# SunS_fixture_EGSE_Connectors.net
KiCad netlist of a schematic drawn in Altium Designer
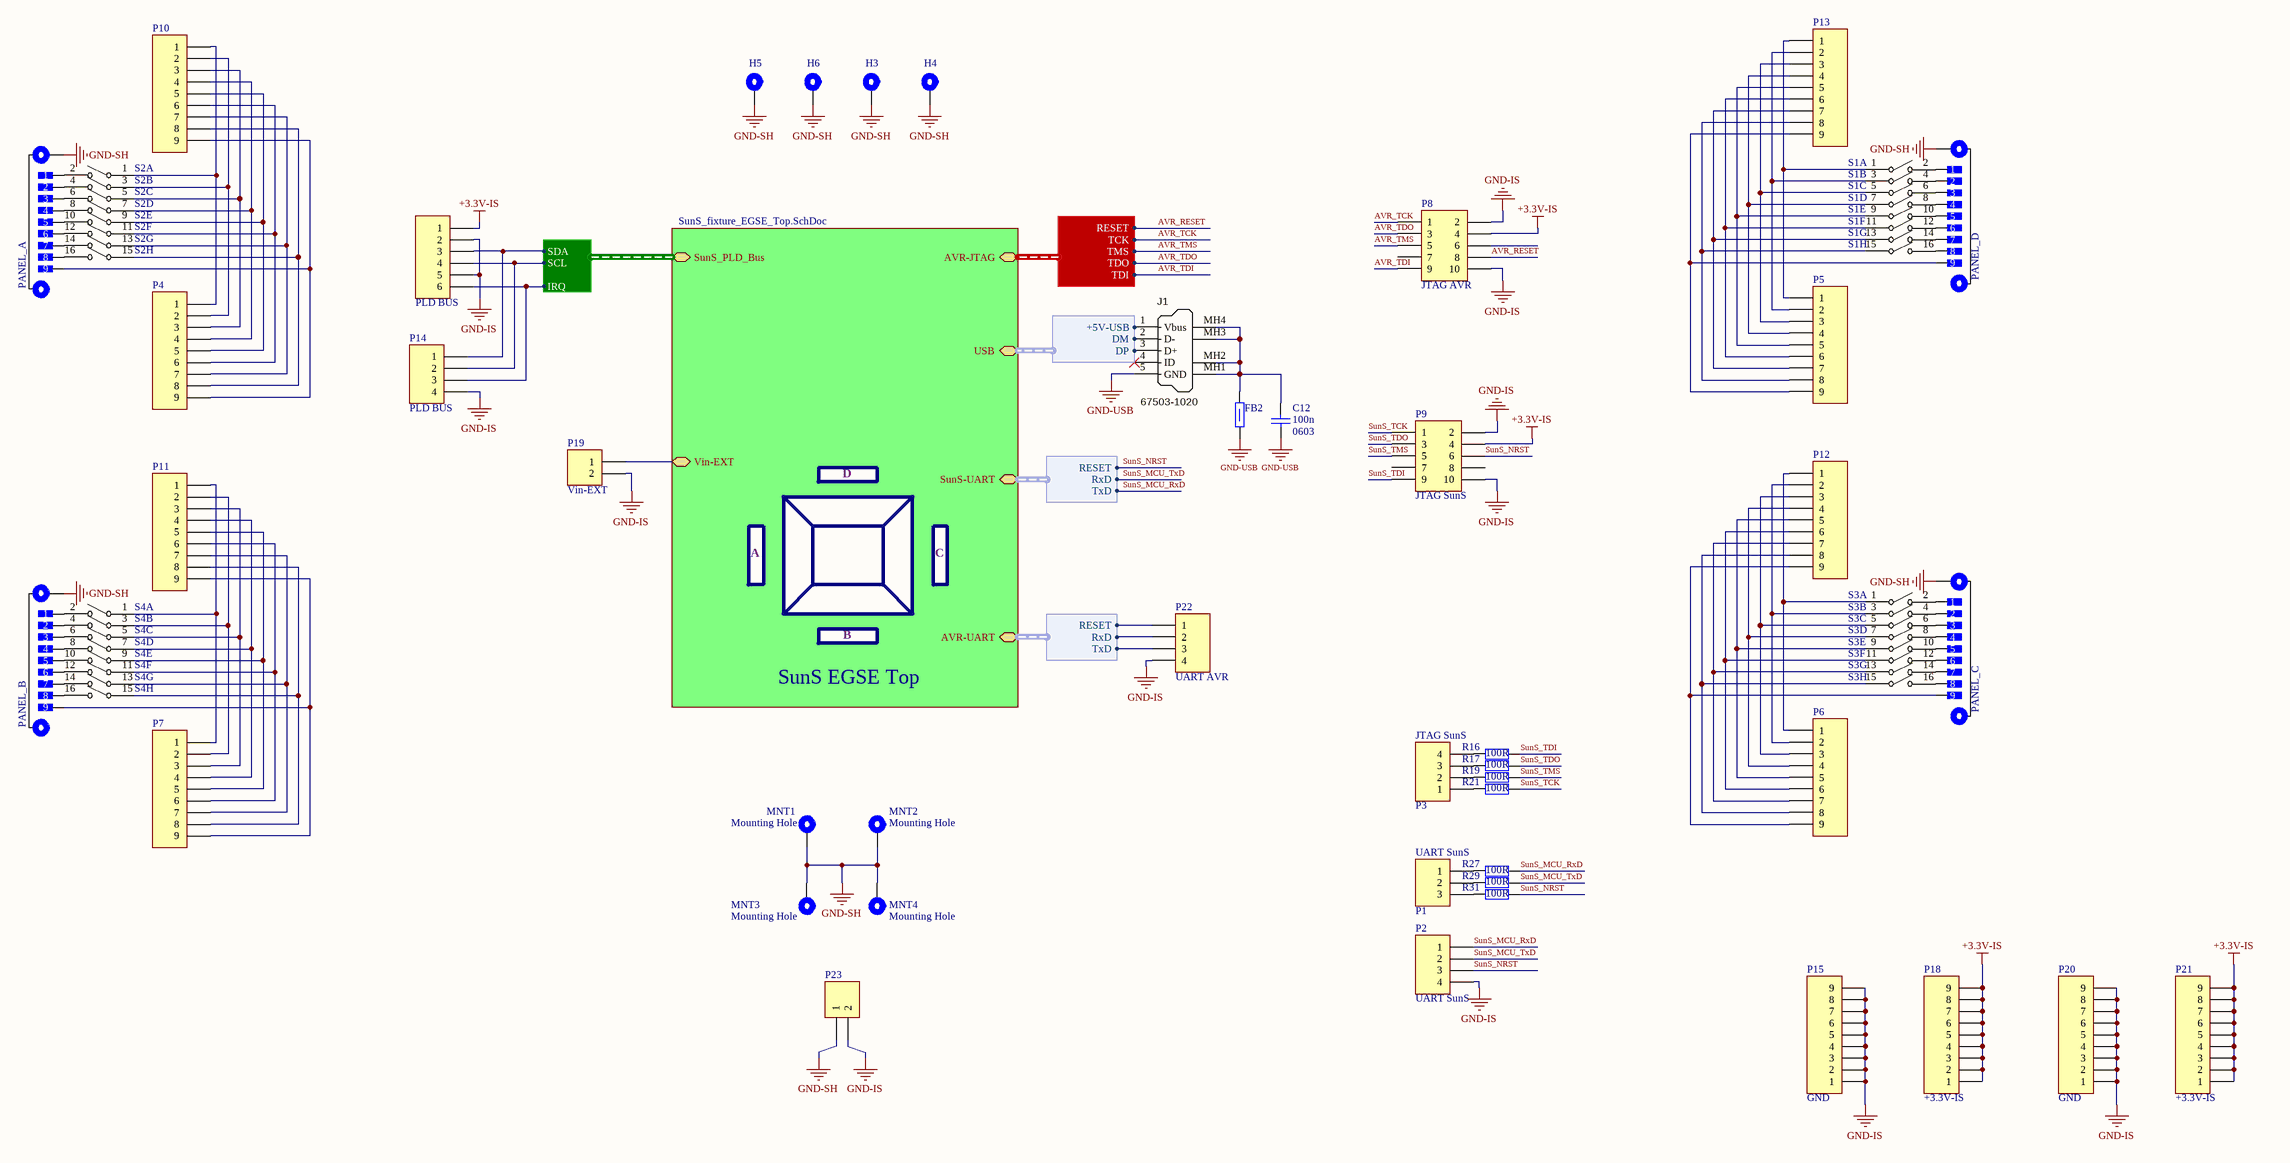
[diagram p0: SunS_fixture_EGSE_Connectors.SchDoc]

(export (version "E")
  (design (tool "Eeschema 10.0.6"))
  (components
    (comp (ref "C12")
      (value "100n")
      (footprint "SMD_Capacitor_0603")
      (description "Cap")
      (fields (field (name "PACKAGE") "0603"))
      (libsource (lib "capacitors") (part "Cap"))
    )
    (comp (ref "FB2")
      (value "120R/100MHz")
      (footprint "SMD_FerriteBead_1206")
      (description "Ferrite bead, 1206, 0.02HM, 3.5A.")
      (fields (field (name "MANUFACTURER") "Murata") (field (name "MANUFACTURERPARTNUMBER") "BLM31PG121SH1L"))
      (libsource (lib "inductors") (part "BLM31PG121SH1L"))
    )
    (comp (ref "H3")
      (value "Mounting Hole")
      (footprint "SunS_PcbMntHole_M2")
      (description "PCB Mounting Hole")
      (libsource (lib "connectors_printed-circuit-board") (part "MntHole"))
    )
    (comp (ref "H4")
      (value "Mounting Hole")
      (footprint "SunS_PcbMntHole_M2")
      (description "PCB Mounting Hole")
      (libsource (lib "connectors_printed-circuit-board") (part "MntHole"))
    )
    (comp (ref "H5")
      (value "Mounting Hole")
      (footprint "SunS_PcbMntHole_M2")
      (description "PCB Mounting Hole")
      (libsource (lib "connectors_printed-circuit-board") (part "MntHole"))
    )
    (comp (ref "H6")
      (value "Mounting Hole")
      (footprint "SunS_PcbMntHole_M2")
      (description "PCB Mounting Hole")
      (libsource (lib "connectors_printed-circuit-board") (part "MntHole"))
    )
    (comp (ref "J1")
      (value "USB_Mini-B")
      (footprint "USB_Mini-B_Molex_SMT")
      (description "Connector SMD USB Type Mini-B")
      (fields (field (name "MANUFACTURER PART NUMBER 1") "67503-1020"))
      (libsource (lib "PBL - Connectors") (part "USB_Mini-B"))
    )
    (comp (ref "MNT1")
      (value "Mounting Hole")
      (footprint "PC-104_PcbMntHole_M3")
      (description "PCB Mounting Hole")
      (libsource (lib "connectors_printed-circuit-board") (part "MntHole"))
    )
    (comp (ref "MNT2")
      (value "Mounting Hole")
      (footprint "PC-104_PcbMntHole_M3")
      (description "PCB Mounting Hole")
      (libsource (lib "connectors_printed-circuit-board") (part "MntHole"))
    )
    (comp (ref "MNT3")
      (value "Mounting Hole")
      (footprint "PC-104_PcbMntHole_M3")
      (description "PCB Mounting Hole")
      (libsource (lib "connectors_printed-circuit-board") (part "MntHole"))
    )
    (comp (ref "MNT4")
      (value "Mounting Hole")
      (footprint "PC-104_PcbMntHole_M3")
      (description "PCB Mounting Hole")
      (libsource (lib "connectors_printed-circuit-board") (part "MntHole"))
    )
    (comp (ref "P1")
      (value "UART SunS")
      (footprint "Mill-Max 854-22-003-10-001101")
      (description "SPRING-LOADED CONNECTORS, 854-22-003-10-001101, 1.27 mm pitch, 1x3pin, THT")
      (libsource (lib "connectors_printed-circuit-board") (part "Mill-Max 854-22-003-10-001101"))
    )
    (comp (ref "P2")
      (value "UART SunS")
      (footprint "HEADER 1x4 MALE")
      (description "Header, 4-Pin")
      (fields (field (name "PUBLISHER") "Altium Limited"))
      (libsource (lib "") (part "Header 4_1"))
    )
    (comp (ref "P3")
      (value "JTAG SunS")
      (footprint "Mill-Max 854-22-004-10-001101")
      (description "SPRING-LOADED CONNECTORS, 854-22-004-10-001101, 1.27 mm pitch, 1x4pin, THT.")
      (libsource (lib "connectors_printed-circuit-board") (part "Mill-Max 854-22-004-10-001101"))
    )
    (comp (ref "P4")
      (value "Mill-Max 854-22-009-10-001101")
      (footprint "Mill-Max 854-22-009-10-001101")
      (description "SPRING-LOADED CONNECTORS, 854-22-009-10-001101, 1.27 mm pitch, 1x9pin, THT.")
      (libsource (lib "") (part "Mill-Max 854-22-009-10-001101_1"))
    )
    (comp (ref "P5")
      (value "Mill-Max 854-22-009-10-001101")
      (footprint "Mill-Max 854-22-009-10-001101")
      (description "SPRING-LOADED CONNECTORS, 854-22-009-10-001101, 1.27 mm pitch, 1x9pin, THT.")
      (libsource (lib "connectors_printed-circuit-board") (part "Mill-Max 854-22-009-10-001101"))
    )
    (comp (ref "P6")
      (value "Mill-Max 854-22-009-10-001101")
      (footprint "Mill-Max 854-22-009-10-001101")
      (description "SPRING-LOADED CONNECTORS, 854-22-009-10-001101, 1.27 mm pitch, 1x9pin, THT.")
      (libsource (lib "connectors_printed-circuit-board") (part "Mill-Max 854-22-009-10-001101"))
    )
    (comp (ref "P7")
      (value "Mill-Max 854-22-009-10-001101")
      (footprint "Mill-Max 854-22-009-10-001101")
      (description "SPRING-LOADED CONNECTORS, 854-22-009-10-001101, 1.27 mm pitch, 1x9pin, THT.")
      (libsource (lib "") (part "Mill-Max 854-22-009-10-001101_1"))
    )
    (comp (ref "P8")
      (value "JTAG AVR")
      (footprint "IDC-10-Male-Socket")
      (description "Header, 5-Pin, Dual row")
      (libsource (lib "connectors_printed-circuit-board") (part "Header 5X2"))
    )
    (comp (ref "P9")
      (value "JTAG SunS")
      (footprint "IDC-10-Male-Socket")
      (description "Header, 5-Pin, Dual row")
      (libsource (lib "connectors_printed-circuit-board") (part "Header 5X2"))
    )
    (comp (ref "P10")
      (value "Header 9")
      (footprint "HEADER 1x9 MALE")
      (description "Header, 9-Pin")
      (fields (field (name "PUBLISHER") "Altium Limited"))
      (libsource (lib "") (part "Header 9_2"))
    )
    (comp (ref "P11")
      (value "Header 9")
      (footprint "HEADER 1x9 MALE")
      (description "Header, 9-Pin")
      (fields (field (name "PUBLISHER") "Altium Limited"))
      (libsource (lib "") (part "Header 9_2"))
    )
    (comp (ref "P12")
      (value "Header 9")
      (footprint "HEADER 1x9 MALE")
      (description "Header, 9-Pin")
      (fields (field (name "PUBLISHER") "Altium Limited"))
      (libsource (lib "") (part "Header 9_1"))
    )
    (comp (ref "P13")
      (value "Header 9")
      (footprint "HEADER 1x9 MALE")
      (description "Header, 9-Pin")
      (fields (field (name "PUBLISHER") "Altium Limited"))
      (libsource (lib "") (part "Header 9_1"))
    )
    (comp (ref "P14")
      (value "PLD BUS")
      (footprint "HEADER 1x4 MALE")
      (description "Header, 4-Pin")
      (fields (field (name "PUBLISHER") "Altium Limited"))
      (libsource (lib "connectors_printed-circuit-board") (part "Header 4x1"))
    )
    (comp (ref "P15")
      (value "GND")
      (footprint "HEADER 1x9 MALE")
      (description "Header, 9-Pin")
      (fields (field (name "PUBLISHER") "Altium Limited"))
      (libsource (lib "connectors_printed-circuit-board") (part "Header 9"))
    )
    (comp (ref "P18")
      (value "+3.3V-IS")
      (footprint "HEADER 1x9 MALE")
      (description "Header, 9-Pin")
      (fields (field (name "PUBLISHER") "Altium Limited"))
      (libsource (lib "connectors_printed-circuit-board") (part "Header 9"))
    )
    (comp (ref "P19")
      (value "Vin-EXT")
      (footprint "HEADER 1X2H Male")
      (description "Header, 2-Pin")
      (fields (field (name "PUBLISHER") "Altium Limited"))
      (libsource (lib "connectors_printed-circuit-board") (part "Header 2"))
    )
    (comp (ref "P20")
      (value "GND")
      (footprint "HEADER 1x9 MALE")
      (description "Header, 9-Pin")
      (fields (field (name "PUBLISHER") "Altium Limited"))
      (libsource (lib "connectors_printed-circuit-board") (part "Header 9"))
    )
    (comp (ref "P21")
      (value "+3.3V-IS")
      (footprint "HEADER 1x9 MALE")
      (description "Header, 9-Pin")
      (fields (field (name "PUBLISHER") "Altium Limited"))
      (libsource (lib "connectors_printed-circuit-board") (part "Header 9"))
    )
    (comp (ref "P22")
      (value "UART AVR")
      (footprint "HEADER 1x4 MALE")
      (description "Header, 4-Pin")
      (fields (field (name "PUBLISHER") "Altium Limited"))
      (libsource (lib "connectors_printed-circuit-board") (part "Header 4"))
    )
    (comp (ref "P23")
      (value "Header 2")
      (footprint "HEADER 1X2 Male")
      (description "Header, 2-Pin")
      (fields (field (name "PUBLISHER") "Altium Limited"))
      (libsource (lib "") (part "Header 2_1"))
    )
    (comp (ref "PANEL_A")
      (value "fixture_ALS_9_pad_1mm_pitch")
      (footprint "fixture_ALS_9_pad_1mm_pitch")
      (description "ALS Panel Fixture Connection")
      (libsource (lib "connectors_printed-circuit-board") (part "fixture_ALS_9_pad_1mm_pitch"))
    )
    (comp (ref "PANEL_B")
      (value "fixture_ALS_9_pad_1mm_pitch")
      (footprint "fixture_ALS_9_pad_1mm_pitch")
      (description "ALS Panel Fixture Connection")
      (libsource (lib "connectors_printed-circuit-board") (part "fixture_ALS_9_pad_1mm_pitch"))
    )
    (comp (ref "PANEL_C")
      (value "fixture_ALS_9_pad_1mm_pitch")
      (footprint "fixture_ALS_9_pad_1mm_pitch")
      (description "ALS Panel Fixture Connection")
      (libsource (lib "") (part "fixture_ALS_9_pad_1mm_pitch_1"))
    )
    (comp (ref "PANEL_D")
      (value "fixture_ALS_9_pad_1mm_pitch")
      (footprint "fixture_ALS_9_pad_1mm_pitch")
      (description "ALS Panel Fixture Connection")
      (libsource (lib "") (part "fixture_ALS_9_pad_1mm_pitch_1"))
    )
    (comp (ref "PLD BUS")
      (value "Mill-Max 854-22-006-10-001101")
      (footprint "Mill-Max 854-22-006-10-001101")
      (description "SPRING-LOADED CONNECTORS, 854-22-006-10-001101, 1.27 mm pitch, 1x6pin, THT.")
      (libsource (lib "connectors_printed-circuit-board") (part "Mill-Max 854-22-006-10-001101"))
    )
    (comp (ref "R16")
      (value "100R")
      (footprint "SMD_Resistor_0603")
      (libsource (lib "resistors") (part "Res"))
    )
    (comp (ref "R17")
      (value "100R")
      (footprint "SMD_Resistor_0603")
      (libsource (lib "resistors") (part "Res"))
    )
    (comp (ref "R19")
      (value "100R")
      (footprint "SMD_Resistor_0603")
      (libsource (lib "resistors") (part "Res"))
    )
    (comp (ref "R21")
      (value "100R")
      (footprint "SMD_Resistor_0603")
      (libsource (lib "resistors") (part "Res"))
    )
    (comp (ref "R27")
      (value "100R")
      (footprint "SMD_Resistor_0603")
      (libsource (lib "resistors") (part "Res"))
    )
    (comp (ref "R29")
      (value "100R")
      (footprint "SMD_Resistor_0603")
      (libsource (lib "resistors") (part "Res"))
    )
    (comp (ref "R31")
      (value "100R")
      (footprint "SMD_Resistor_0603")
      (libsource (lib "resistors") (part "Res"))
    )
    (comp (ref "S1") (value "MCEPM-08") (footprint "MCEPM-08") (libsource (lib "switches") (part "MCEPM-08")))
    (comp (ref "S2") (value "MCEPM-08") (footprint "MCEPM-08") (libsource (lib "") (part "MCEPM-08_7")))
    (comp (ref "S3") (value "MCEPM-08") (footprint "MCEPM-08") (libsource (lib "switches") (part "MCEPM-08")))
    (comp (ref "S4") (value "MCEPM-08") (footprint "MCEPM-08") (libsource (lib "") (part "MCEPM-08_5")))
  )
  (nets
    (net (code "5") (name "+3.3V-IS") (class "Default")
      (node (ref "P18") (pin "1") (pinfunction "1_1") (pintype "passive"))
      (node (ref "P18") (pin "2") (pinfunction "2_2") (pintype "passive"))
      (node (ref "P18") (pin "3") (pinfunction "3_3") (pintype "passive"))
      (node (ref "P18") (pin "4") (pinfunction "4_4") (pintype "passive"))
      (node (ref "P18") (pin "5") (pinfunction "5_5") (pintype "passive"))
      (node (ref "P18") (pin "6") (pinfunction "6_6") (pintype "passive"))
      (node (ref "P18") (pin "7") (pinfunction "7_7") (pintype "passive"))
      (node (ref "P18") (pin "8") (pinfunction "8_8") (pintype "passive"))
      (node (ref "P18") (pin "9") (pinfunction "9_9") (pintype "passive"))
      (node (ref "P21") (pin "1") (pinfunction "1_1") (pintype "passive"))
      (node (ref "P21") (pin "2") (pinfunction "2_2") (pintype "passive"))
      (node (ref "P21") (pin "3") (pinfunction "3_3") (pintype "passive"))
      (node (ref "P21") (pin "4") (pinfunction "4_4") (pintype "passive"))
      (node (ref "P21") (pin "5") (pinfunction "5_5") (pintype "passive"))
      (node (ref "P21") (pin "6") (pinfunction "6_6") (pintype "passive"))
      (node (ref "P21") (pin "7") (pinfunction "7_7") (pintype "passive"))
      (node (ref "P21") (pin "8") (pinfunction "8_8") (pintype "passive"))
      (node (ref "P21") (pin "9") (pinfunction "9_9") (pintype "passive"))
      (node (ref "P8") (pin "4") (pinfunction "4_4") (pintype "passive"))
      (node (ref "P9") (pin "4") (pinfunction "4_4") (pintype "passive"))
      (node (ref "PLD BUS") (pin "1") (pinfunction "1_1") (pintype "passive"))
    )
    (net (code "6") (name "/+5V-USB") (class "Default")
      (node (ref "J1") (pin "1") (pinfunction "Vbus_1") (pintype "passive"))
    )
    (net (code "7") (name "/AVR_RESET") (class "Default")
      (node (ref "P8") (pin "8") (pinfunction "8_8") (pintype "passive"))
    )
    (net (code "8") (name "/AVR_TCK") (class "Default")
      (node (ref "P8") (pin "1") (pinfunction "1_1") (pintype "passive"))
    )
    (net (code "9") (name "/AVR_TDI") (class "Default")
      (node (ref "P8") (pin "9") (pinfunction "9_9") (pintype "passive"))
    )
    (net (code "10") (name "/AVR_TDO") (class "Default")
      (node (ref "P8") (pin "3") (pinfunction "3_3") (pintype "passive"))
    )
    (net (code "11") (name "/AVR_TMS") (class "Default")
      (node (ref "P8") (pin "5") (pinfunction "5_5") (pintype "passive"))
    )
    (net (code "12") (name "/DM") (class "Default")
      (node (ref "J1") (pin "2") (pinfunction "D-_2") (pintype "passive"))
    )
    (net (code "13") (name "/DP") (class "Default")
      (node (ref "J1") (pin "3") (pinfunction "D+_3") (pintype "passive"))
    )
    (net (code "14") (name "/IRQ") (class "Default")
      (node (ref "P14") (pin "3") (pinfunction "3_3") (pintype "passive"))
      (node (ref "PLD BUS") (pin "6") (pinfunction "6_6") (pintype "passive"))
    )
    (net (code "15") (name "/SCL") (class "Default")
      (node (ref "P14") (pin "2") (pinfunction "2_2") (pintype "passive"))
      (node (ref "PLD BUS") (pin "4") (pinfunction "4_4") (pintype "passive"))
    )
    (net (code "16") (name "/SDA") (class "Default")
      (node (ref "P14") (pin "1") (pinfunction "1_1") (pintype "passive"))
      (node (ref "PLD BUS") (pin "3") (pinfunction "3_3") (pintype "passive"))
    )
    (net (code "17") (name "/SunS_MCU_RxD") (class "Default")
      (node (ref "P2") (pin "1") (pinfunction "1_1") (pintype "passive"))
      (node (ref "R27") (pin "1") (pinfunction "1_1") (pintype "passive"))
    )
    (net (code "18") (name "/SunS_MCU_TxD") (class "Default")
      (node (ref "P2") (pin "2") (pinfunction "2_2") (pintype "passive"))
      (node (ref "R29") (pin "1") (pinfunction "1_1") (pintype "passive"))
    )
    (net (code "19") (name "/SunS_NRST") (class "Default")
      (node (ref "P2") (pin "3") (pinfunction "3_3") (pintype "passive"))
      (node (ref "P9") (pin "6") (pinfunction "6_6") (pintype "passive"))
      (node (ref "R31") (pin "1") (pinfunction "1_1") (pintype "passive"))
    )
    (net (code "20") (name "/SunS_TCK") (class "Default")
      (node (ref "P9") (pin "1") (pinfunction "1_1") (pintype "passive"))
      (node (ref "R21") (pin "1") (pinfunction "1_1") (pintype "passive"))
    )
    (net (code "21") (name "/SunS_TDI") (class "Default")
      (node (ref "P9") (pin "9") (pinfunction "9_9") (pintype "passive"))
      (node (ref "R16") (pin "1") (pinfunction "1_1") (pintype "passive"))
    )
    (net (code "22") (name "/SunS_TDO") (class "Default")
      (node (ref "P9") (pin "3") (pinfunction "3_3") (pintype "passive"))
      (node (ref "R17") (pin "1") (pinfunction "1_1") (pintype "passive"))
    )
    (net (code "23") (name "/SunS_TMS") (class "Default")
      (node (ref "P9") (pin "5") (pinfunction "5_5") (pintype "passive"))
      (node (ref "R19") (pin "1") (pinfunction "1_1") (pintype "passive"))
    )
    (net (code "24") (name "/Vin-EXT") (class "Default")
      (node (ref "P19") (pin "1") (pinfunction "1_1") (pintype "passive"))
    )
    (net (code "29") (name "GND-IS") (class "Default")
      (node (ref "P14") (pin "4") (pinfunction "4_4") (pintype "passive"))
      (node (ref "P15") (pin "1") (pinfunction "1_1") (pintype "passive"))
      (node (ref "P15") (pin "2") (pinfunction "2_2") (pintype "passive"))
      (node (ref "P15") (pin "3") (pinfunction "3_3") (pintype "passive"))
      (node (ref "P15") (pin "4") (pinfunction "4_4") (pintype "passive"))
      (node (ref "P15") (pin "5") (pinfunction "5_5") (pintype "passive"))
      (node (ref "P15") (pin "6") (pinfunction "6_6") (pintype "passive"))
      (node (ref "P15") (pin "7") (pinfunction "7_7") (pintype "passive"))
      (node (ref "P15") (pin "8") (pinfunction "8_8") (pintype "passive"))
      (node (ref "P15") (pin "9") (pinfunction "9_9") (pintype "passive"))
      (node (ref "P19") (pin "2") (pinfunction "2_2") (pintype "passive"))
      (node (ref "P2") (pin "4") (pinfunction "4_4") (pintype "passive"))
      (node (ref "P20") (pin "1") (pinfunction "1_1") (pintype "passive"))
      (node (ref "P20") (pin "2") (pinfunction "2_2") (pintype "passive"))
      (node (ref "P20") (pin "3") (pinfunction "3_3") (pintype "passive"))
      (node (ref "P20") (pin "4") (pinfunction "4_4") (pintype "passive"))
      (node (ref "P20") (pin "5") (pinfunction "5_5") (pintype "passive"))
      (node (ref "P20") (pin "6") (pinfunction "6_6") (pintype "passive"))
      (node (ref "P20") (pin "7") (pinfunction "7_7") (pintype "passive"))
      (node (ref "P20") (pin "8") (pinfunction "8_8") (pintype "passive"))
      (node (ref "P20") (pin "9") (pinfunction "9_9") (pintype "passive"))
      (node (ref "P22") (pin "4") (pinfunction "4_4") (pintype "passive"))
      (node (ref "P23") (pin "2") (pinfunction "2_2") (pintype "passive"))
      (node (ref "P8") (pin "10") (pinfunction "10_10") (pintype "passive"))
      (node (ref "P8") (pin "2") (pinfunction "2_2") (pintype "passive"))
      (node (ref "P9") (pin "10") (pinfunction "10_10") (pintype "passive"))
      (node (ref "P9") (pin "2") (pinfunction "2_2") (pintype "passive"))
      (node (ref "PLD BUS") (pin "2") (pinfunction "2_2") (pintype "passive"))
      (node (ref "PLD BUS") (pin "5") (pinfunction "5_5") (pintype "passive"))
    )
    (net (code "30") (name "GND-SH") (class "Default")
      (node (ref "H3") (pin "1") (pinfunction "1_1") (pintype "passive"))
      (node (ref "H4") (pin "1") (pinfunction "1_1") (pintype "passive"))
      (node (ref "H5") (pin "1") (pinfunction "1_1") (pintype "passive"))
      (node (ref "H6") (pin "1") (pinfunction "1_1") (pintype "passive"))
      (node (ref "MNT1") (pin "1") (pinfunction "1_1") (pintype "passive"))
      (node (ref "MNT2") (pin "1") (pinfunction "1_1") (pintype "passive"))
      (node (ref "MNT3") (pin "1") (pinfunction "1_1") (pintype "passive"))
      (node (ref "MNT4") (pin "1") (pinfunction "1_1") (pintype "passive"))
      (node (ref "P23") (pin "1") (pinfunction "1_1") (pintype "passive"))
      (node (ref "PANEL_A") (pin "0") (pinfunction "0_0") (pintype "passive"))
      (node (ref "PANEL_B") (pin "0") (pinfunction "0_0") (pintype "passive"))
      (node (ref "PANEL_C") (pin "0") (pinfunction "0_0") (pintype "passive"))
      (node (ref "PANEL_D") (pin "0") (pinfunction "0_0") (pintype "passive"))
    )
    (net (code "31") (name "GND-USB") (class "Default")
      (node (ref "C12") (pin "2") (pinfunction "2_2") (pintype "passive"))
      (node (ref "FB2") (pin "2") (pinfunction "2_2") (pintype "passive"))
      (node (ref "J1") (pin "5") (pinfunction "GND_5") (pintype "passive"))
    )
    (net (code "32") (name "Net-(C12-Pad1)") (class "Default")
      (node (ref "C12") (pin "1") (pinfunction "1_1") (pintype "passive"))
      (node (ref "FB2") (pin "1") (pinfunction "1_1") (pintype "passive"))
      (node (ref "J1") (pin "MH1") (pinfunction "Shell_MH1") (pintype "passive"))
      (node (ref "J1") (pin "MH2") (pinfunction "Shell_MH2") (pintype "passive"))
      (node (ref "J1") (pin "MH3") (pinfunction "Shell_MH3") (pintype "passive"))
      (node (ref "J1") (pin "MH4") (pinfunction "Shell_MH4") (pintype "passive"))
    )
    (net (code "33") (name "Net-(P1-Pad1)") (class "Default")
      (node (ref "P1") (pin "1") (pinfunction "1_1") (pintype "passive"))
      (node (ref "R27") (pin "2") (pinfunction "2_2") (pintype "passive"))
    )
    (net (code "34") (name "Net-(P1-Pad2)") (class "Default")
      (node (ref "P1") (pin "2") (pinfunction "2_2") (pintype "passive"))
      (node (ref "R29") (pin "2") (pinfunction "2_2") (pintype "passive"))
    )
    (net (code "35") (name "Net-(P1-Pad3)") (class "Default")
      (node (ref "P1") (pin "3") (pinfunction "3_3") (pintype "passive"))
      (node (ref "R31") (pin "2") (pinfunction "2_2") (pintype "passive"))
    )
    (net (code "36") (name "Net-(P3-Pad1)") (class "Default")
      (node (ref "P3") (pin "1") (pinfunction "1_1") (pintype "passive"))
      (node (ref "R21") (pin "2") (pinfunction "2_2") (pintype "passive"))
    )
    (net (code "37") (name "Net-(P3-Pad2)") (class "Default")
      (node (ref "P3") (pin "2") (pinfunction "2_2") (pintype "passive"))
      (node (ref "R19") (pin "2") (pinfunction "2_2") (pintype "passive"))
    )
    (net (code "38") (name "Net-(P3-Pad3)") (class "Default")
      (node (ref "P3") (pin "3") (pinfunction "3_3") (pintype "passive"))
      (node (ref "R17") (pin "2") (pinfunction "2_2") (pintype "passive"))
    )
    (net (code "39") (name "Net-(P3-Pad4)") (class "Default")
      (node (ref "P3") (pin "4") (pinfunction "4_4") (pintype "passive"))
      (node (ref "R16") (pin "2") (pinfunction "2_2") (pintype "passive"))
    )
    (net (code "40") (name "Net-(P10-Pad1)") (class "Default")
      (node (ref "P10") (pin "1") (pinfunction "1_1") (pintype "passive"))
      (node (ref "P4") (pin "1") (pinfunction "1_1") (pintype "passive"))
      (node (ref "S2") (pin "1") (pinfunction "1_1") (pintype "passive"))
    )
    (net (code "41") (name "Net-(P10-Pad2)") (class "Default")
      (node (ref "P10") (pin "2") (pinfunction "2_2") (pintype "passive"))
      (node (ref "P4") (pin "2") (pinfunction "2_2") (pintype "passive"))
      (node (ref "S2") (pin "3") (pinfunction "3_3") (pintype "passive"))
    )
    (net (code "42") (name "Net-(P10-Pad3)") (class "Default")
      (node (ref "P10") (pin "3") (pinfunction "3_3") (pintype "passive"))
      (node (ref "P4") (pin "3") (pinfunction "3_3") (pintype "passive"))
      (node (ref "S2") (pin "5") (pinfunction "5_5") (pintype "passive"))
    )
    (net (code "43") (name "Net-(P10-Pad4)") (class "Default")
      (node (ref "P10") (pin "4") (pinfunction "4_4") (pintype "passive"))
      (node (ref "P4") (pin "4") (pinfunction "4_4") (pintype "passive"))
      (node (ref "S2") (pin "7") (pinfunction "7_7") (pintype "passive"))
    )
    (net (code "44") (name "Net-(P10-Pad5)") (class "Default")
      (node (ref "P10") (pin "5") (pinfunction "5_5") (pintype "passive"))
      (node (ref "P4") (pin "5") (pinfunction "5_5") (pintype "passive"))
      (node (ref "S2") (pin "9") (pinfunction "9_9") (pintype "passive"))
    )
    (net (code "45") (name "Net-(P10-Pad6)") (class "Default")
      (node (ref "P10") (pin "6") (pinfunction "6_6") (pintype "passive"))
      (node (ref "P4") (pin "6") (pinfunction "6_6") (pintype "passive"))
      (node (ref "S2") (pin "11") (pinfunction "11_11") (pintype "passive"))
    )
    (net (code "46") (name "Net-(P10-Pad7)") (class "Default")
      (node (ref "P10") (pin "7") (pinfunction "7_7") (pintype "passive"))
      (node (ref "P4") (pin "7") (pinfunction "7_7") (pintype "passive"))
      (node (ref "S2") (pin "13") (pinfunction "13_13") (pintype "passive"))
    )
    (net (code "47") (name "Net-(P10-Pad8)") (class "Default")
      (node (ref "P10") (pin "8") (pinfunction "8_8") (pintype "passive"))
      (node (ref "P4") (pin "8") (pinfunction "8_8") (pintype "passive"))
      (node (ref "S2") (pin "15") (pinfunction "15_15") (pintype "passive"))
    )
    (net (code "48") (name "Net-(P10-Pad9)") (class "Default")
      (node (ref "P10") (pin "9") (pinfunction "9_9") (pintype "passive"))
      (node (ref "P4") (pin "9") (pinfunction "9_9") (pintype "passive"))
      (node (ref "PANEL_A") (pin "9") (pinfunction "9_9") (pintype "passive"))
    )
    (net (code "49") (name "Net-(P11-Pad1)") (class "Default")
      (node (ref "P11") (pin "1") (pinfunction "1_1") (pintype "passive"))
      (node (ref "P7") (pin "1") (pinfunction "1_1") (pintype "passive"))
      (node (ref "S4") (pin "1") (pinfunction "1_1") (pintype "passive"))
    )
    (net (code "50") (name "Net-(P11-Pad2)") (class "Default")
      (node (ref "P11") (pin "2") (pinfunction "2_2") (pintype "passive"))
      (node (ref "P7") (pin "2") (pinfunction "2_2") (pintype "passive"))
      (node (ref "S4") (pin "3") (pinfunction "3_3") (pintype "passive"))
    )
    (net (code "51") (name "Net-(P11-Pad3)") (class "Default")
      (node (ref "P11") (pin "3") (pinfunction "3_3") (pintype "passive"))
      (node (ref "P7") (pin "3") (pinfunction "3_3") (pintype "passive"))
      (node (ref "S4") (pin "5") (pinfunction "5_5") (pintype "passive"))
    )
    (net (code "52") (name "Net-(P11-Pad4)") (class "Default")
      (node (ref "P11") (pin "4") (pinfunction "4_4") (pintype "passive"))
      (node (ref "P7") (pin "4") (pinfunction "4_4") (pintype "passive"))
      (node (ref "S4") (pin "7") (pinfunction "7_7") (pintype "passive"))
    )
    (net (code "53") (name "Net-(P11-Pad5)") (class "Default")
      (node (ref "P11") (pin "5") (pinfunction "5_5") (pintype "passive"))
      (node (ref "P7") (pin "5") (pinfunction "5_5") (pintype "passive"))
      (node (ref "S4") (pin "9") (pinfunction "9_9") (pintype "passive"))
    )
    (net (code "54") (name "Net-(P11-Pad6)") (class "Default")
      (node (ref "P11") (pin "6") (pinfunction "6_6") (pintype "passive"))
      (node (ref "P7") (pin "6") (pinfunction "6_6") (pintype "passive"))
      (node (ref "S4") (pin "11") (pinfunction "11_11") (pintype "passive"))
    )
    (net (code "55") (name "Net-(P11-Pad7)") (class "Default")
      (node (ref "P11") (pin "7") (pinfunction "7_7") (pintype "passive"))
      (node (ref "P7") (pin "7") (pinfunction "7_7") (pintype "passive"))
      (node (ref "S4") (pin "13") (pinfunction "13_13") (pintype "passive"))
    )
    (net (code "56") (name "Net-(P11-Pad8)") (class "Default")
      (node (ref "P11") (pin "8") (pinfunction "8_8") (pintype "passive"))
      (node (ref "P7") (pin "8") (pinfunction "8_8") (pintype "passive"))
      (node (ref "S4") (pin "15") (pinfunction "15_15") (pintype "passive"))
    )
    (net (code "57") (name "Net-(P11-Pad9)") (class "Default")
      (node (ref "P11") (pin "9") (pinfunction "9_9") (pintype "passive"))
      (node (ref "P7") (pin "9") (pinfunction "9_9") (pintype "passive"))
      (node (ref "PANEL_B") (pin "9") (pinfunction "9_9") (pintype "passive"))
    )
    (net (code "58") (name "Net-(P12-Pad1)") (class "Default")
      (node (ref "P12") (pin "1") (pinfunction "1_1") (pintype "passive"))
      (node (ref "P6") (pin "1") (pinfunction "1_1") (pintype "passive"))
      (node (ref "S3") (pin "1") (pinfunction "1_1") (pintype "passive"))
    )
    (net (code "59") (name "Net-(P12-Pad2)") (class "Default")
      (node (ref "P12") (pin "2") (pinfunction "2_2") (pintype "passive"))
      (node (ref "P6") (pin "2") (pinfunction "2_2") (pintype "passive"))
      (node (ref "S3") (pin "3") (pinfunction "3_3") (pintype "passive"))
    )
    (net (code "60") (name "Net-(P12-Pad3)") (class "Default")
      (node (ref "P12") (pin "3") (pinfunction "3_3") (pintype "passive"))
      (node (ref "P6") (pin "3") (pinfunction "3_3") (pintype "passive"))
      (node (ref "S3") (pin "5") (pinfunction "5_5") (pintype "passive"))
    )
    (net (code "61") (name "Net-(P12-Pad4)") (class "Default")
      (node (ref "P12") (pin "4") (pinfunction "4_4") (pintype "passive"))
      (node (ref "P6") (pin "4") (pinfunction "4_4") (pintype "passive"))
      (node (ref "S3") (pin "7") (pinfunction "7_7") (pintype "passive"))
    )
    (net (code "62") (name "Net-(P12-Pad5)") (class "Default")
      (node (ref "P12") (pin "5") (pinfunction "5_5") (pintype "passive"))
      (node (ref "P6") (pin "5") (pinfunction "5_5") (pintype "passive"))
      (node (ref "S3") (pin "9") (pinfunction "9_9") (pintype "passive"))
    )
    (net (code "63") (name "Net-(P12-Pad6)") (class "Default")
      (node (ref "P12") (pin "6") (pinfunction "6_6") (pintype "passive"))
      (node (ref "P6") (pin "6") (pinfunction "6_6") (pintype "passive"))
      (node (ref "S3") (pin "11") (pinfunction "11_11") (pintype "passive"))
    )
    (net (code "64") (name "Net-(P12-Pad7)") (class "Default")
      (node (ref "P12") (pin "7") (pinfunction "7_7") (pintype "passive"))
      (node (ref "P6") (pin "7") (pinfunction "7_7") (pintype "passive"))
      (node (ref "S3") (pin "13") (pinfunction "13_13") (pintype "passive"))
    )
    (net (code "65") (name "Net-(P12-Pad8)") (class "Default")
      (node (ref "P12") (pin "8") (pinfunction "8_8") (pintype "passive"))
      (node (ref "P6") (pin "8") (pinfunction "8_8") (pintype "passive"))
      (node (ref "S3") (pin "15") (pinfunction "15_15") (pintype "passive"))
    )
    (net (code "66") (name "Net-(P12-Pad9)") (class "Default")
      (node (ref "P12") (pin "9") (pinfunction "9_9") (pintype "passive"))
      (node (ref "P6") (pin "9") (pinfunction "9_9") (pintype "passive"))
      (node (ref "PANEL_C") (pin "9") (pinfunction "9_9") (pintype "passive"))
    )
    (net (code "67") (name "Net-(P13-Pad1)") (class "Default")
      (node (ref "P13") (pin "1") (pinfunction "1_1") (pintype "passive"))
      (node (ref "P5") (pin "1") (pinfunction "1_1") (pintype "passive"))
      (node (ref "S1") (pin "1") (pinfunction "1_1") (pintype "passive"))
    )
    (net (code "68") (name "Net-(P13-Pad2)") (class "Default")
      (node (ref "P13") (pin "2") (pinfunction "2_2") (pintype "passive"))
      (node (ref "P5") (pin "2") (pinfunction "2_2") (pintype "passive"))
      (node (ref "S1") (pin "3") (pinfunction "3_3") (pintype "passive"))
    )
    (net (code "69") (name "Net-(P13-Pad3)") (class "Default")
      (node (ref "P13") (pin "3") (pinfunction "3_3") (pintype "passive"))
      (node (ref "P5") (pin "3") (pinfunction "3_3") (pintype "passive"))
      (node (ref "S1") (pin "5") (pinfunction "5_5") (pintype "passive"))
    )
    (net (code "70") (name "Net-(P13-Pad4)") (class "Default")
      (node (ref "P13") (pin "4") (pinfunction "4_4") (pintype "passive"))
      (node (ref "P5") (pin "4") (pinfunction "4_4") (pintype "passive"))
      (node (ref "S1") (pin "7") (pinfunction "7_7") (pintype "passive"))
    )
    (net (code "71") (name "Net-(P13-Pad5)") (class "Default")
      (node (ref "P13") (pin "5") (pinfunction "5_5") (pintype "passive"))
      (node (ref "P5") (pin "5") (pinfunction "5_5") (pintype "passive"))
      (node (ref "S1") (pin "9") (pinfunction "9_9") (pintype "passive"))
    )
    (net (code "72") (name "Net-(P13-Pad6)") (class "Default")
      (node (ref "P13") (pin "6") (pinfunction "6_6") (pintype "passive"))
      (node (ref "P5") (pin "6") (pinfunction "6_6") (pintype "passive"))
      (node (ref "S1") (pin "11") (pinfunction "11_11") (pintype "passive"))
    )
    (net (code "73") (name "Net-(P13-Pad7)") (class "Default")
      (node (ref "P13") (pin "7") (pinfunction "7_7") (pintype "passive"))
      (node (ref "P5") (pin "7") (pinfunction "7_7") (pintype "passive"))
      (node (ref "S1") (pin "13") (pinfunction "13_13") (pintype "passive"))
    )
    (net (code "74") (name "Net-(P13-Pad8)") (class "Default")
      (node (ref "P13") (pin "8") (pinfunction "8_8") (pintype "passive"))
      (node (ref "P5") (pin "8") (pinfunction "8_8") (pintype "passive"))
      (node (ref "S1") (pin "15") (pinfunction "15_15") (pintype "passive"))
    )
    (net (code "75") (name "Net-(P13-Pad9)") (class "Default")
      (node (ref "P13") (pin "9") (pinfunction "9_9") (pintype "passive"))
      (node (ref "P5") (pin "9") (pinfunction "9_9") (pintype "passive"))
      (node (ref "PANEL_D") (pin "9") (pinfunction "9_9") (pintype "passive"))
    )
    (net (code "76") (name "Net-(PANEL_A-Pad1)") (class "Default")
      (node (ref "PANEL_A") (pin "1") (pinfunction "1_1") (pintype "passive"))
      (node (ref "S2") (pin "2") (pinfunction "2_2") (pintype "passive"))
    )
    (net (code "77") (name "Net-(PANEL_A-Pad2)") (class "Default")
      (node (ref "PANEL_A") (pin "2") (pinfunction "2_2") (pintype "passive"))
      (node (ref "S2") (pin "4") (pinfunction "4_4") (pintype "passive"))
    )
    (net (code "78") (name "Net-(PANEL_A-Pad3)") (class "Default")
      (node (ref "PANEL_A") (pin "3") (pinfunction "3_3") (pintype "passive"))
      (node (ref "S2") (pin "6") (pinfunction "6_6") (pintype "passive"))
    )
    (net (code "79") (name "Net-(PANEL_A-Pad4)") (class "Default")
      (node (ref "PANEL_A") (pin "4") (pinfunction "4_4") (pintype "passive"))
      (node (ref "S2") (pin "8") (pinfunction "8_8") (pintype "passive"))
    )
    (net (code "80") (name "Net-(PANEL_A-Pad5)") (class "Default")
      (node (ref "PANEL_A") (pin "5") (pinfunction "5_5") (pintype "passive"))
      (node (ref "S2") (pin "10") (pinfunction "10_10") (pintype "passive"))
    )
    (net (code "81") (name "Net-(PANEL_A-Pad6)") (class "Default")
      (node (ref "PANEL_A") (pin "6") (pinfunction "6_6") (pintype "passive"))
      (node (ref "S2") (pin "12") (pinfunction "12_12") (pintype "passive"))
    )
    (net (code "82") (name "Net-(PANEL_A-Pad7)") (class "Default")
      (node (ref "PANEL_A") (pin "7") (pinfunction "7_7") (pintype "passive"))
      (node (ref "S2") (pin "14") (pinfunction "14_14") (pintype "passive"))
    )
    (net (code "83") (name "Net-(PANEL_A-Pad8)") (class "Default")
      (node (ref "PANEL_A") (pin "8") (pinfunction "8_8") (pintype "passive"))
      (node (ref "S2") (pin "16") (pinfunction "16_16") (pintype "passive"))
    )
    (net (code "84") (name "Net-(PANEL_B-Pad1)") (class "Default")
      (node (ref "PANEL_B") (pin "1") (pinfunction "1_1") (pintype "passive"))
      (node (ref "S4") (pin "2") (pinfunction "2_2") (pintype "passive"))
    )
    (net (code "85") (name "Net-(PANEL_B-Pad2)") (class "Default")
      (node (ref "PANEL_B") (pin "2") (pinfunction "2_2") (pintype "passive"))
      (node (ref "S4") (pin "4") (pinfunction "4_4") (pintype "passive"))
    )
    (net (code "86") (name "Net-(PANEL_B-Pad3)") (class "Default")
      (node (ref "PANEL_B") (pin "3") (pinfunction "3_3") (pintype "passive"))
      (node (ref "S4") (pin "6") (pinfunction "6_6") (pintype "passive"))
    )
    (net (code "87") (name "Net-(PANEL_B-Pad4)") (class "Default")
      (node (ref "PANEL_B") (pin "4") (pinfunction "4_4") (pintype "passive"))
      (node (ref "S4") (pin "8") (pinfunction "8_8") (pintype "passive"))
    )
    (net (code "88") (name "Net-(PANEL_B-Pad5)") (class "Default")
      (node (ref "PANEL_B") (pin "5") (pinfunction "5_5") (pintype "passive"))
      (node (ref "S4") (pin "10") (pinfunction "10_10") (pintype "passive"))
    )
    (net (code "89") (name "Net-(PANEL_B-Pad6)") (class "Default")
      (node (ref "PANEL_B") (pin "6") (pinfunction "6_6") (pintype "passive"))
      (node (ref "S4") (pin "12") (pinfunction "12_12") (pintype "passive"))
    )
    (net (code "90") (name "Net-(PANEL_B-Pad7)") (class "Default")
      (node (ref "PANEL_B") (pin "7") (pinfunction "7_7") (pintype "passive"))
      (node (ref "S4") (pin "14") (pinfunction "14_14") (pintype "passive"))
    )
    (net (code "91") (name "Net-(PANEL_B-Pad8)") (class "Default")
      (node (ref "PANEL_B") (pin "8") (pinfunction "8_8") (pintype "passive"))
      (node (ref "S4") (pin "16") (pinfunction "16_16") (pintype "passive"))
    )
    (net (code "92") (name "Net-(PANEL_C-Pad1)") (class "Default")
      (node (ref "PANEL_C") (pin "1") (pinfunction "1_1") (pintype "passive"))
      (node (ref "S3") (pin "2") (pinfunction "2_2") (pintype "passive"))
    )
    (net (code "93") (name "Net-(PANEL_C-Pad2)") (class "Default")
      (node (ref "PANEL_C") (pin "2") (pinfunction "2_2") (pintype "passive"))
      (node (ref "S3") (pin "4") (pinfunction "4_4") (pintype "passive"))
    )
    (net (code "94") (name "Net-(PANEL_C-Pad3)") (class "Default")
      (node (ref "PANEL_C") (pin "3") (pinfunction "3_3") (pintype "passive"))
      (node (ref "S3") (pin "6") (pinfunction "6_6") (pintype "passive"))
    )
    (net (code "95") (name "Net-(PANEL_C-Pad4)") (class "Default")
      (node (ref "PANEL_C") (pin "4") (pinfunction "4_4") (pintype "passive"))
      (node (ref "S3") (pin "8") (pinfunction "8_8") (pintype "passive"))
    )
    (net (code "96") (name "Net-(PANEL_C-Pad5)") (class "Default")
      (node (ref "PANEL_C") (pin "5") (pinfunction "5_5") (pintype "passive"))
      (node (ref "S3") (pin "10") (pinfunction "10_10") (pintype "passive"))
    )
    (net (code "97") (name "Net-(PANEL_C-Pad6)") (class "Default")
      (node (ref "PANEL_C") (pin "6") (pinfunction "6_6") (pintype "passive"))
      (node (ref "S3") (pin "12") (pinfunction "12_12") (pintype "passive"))
    )
    (net (code "98") (name "Net-(PANEL_C-Pad7)") (class "Default")
      (node (ref "PANEL_C") (pin "7") (pinfunction "7_7") (pintype "passive"))
      (node (ref "S3") (pin "14") (pinfunction "14_14") (pintype "passive"))
    )
    (net (code "99") (name "Net-(PANEL_C-Pad8)") (class "Default")
      (node (ref "PANEL_C") (pin "8") (pinfunction "8_8") (pintype "passive"))
      (node (ref "S3") (pin "16") (pinfunction "16_16") (pintype "passive"))
    )
    (net (code "100") (name "Net-(PANEL_D-Pad1)") (class "Default")
      (node (ref "PANEL_D") (pin "1") (pinfunction "1_1") (pintype "passive"))
      (node (ref "S1") (pin "2") (pinfunction "2_2") (pintype "passive"))
    )
    (net (code "101") (name "Net-(PANEL_D-Pad2)") (class "Default")
      (node (ref "PANEL_D") (pin "2") (pinfunction "2_2") (pintype "passive"))
      (node (ref "S1") (pin "4") (pinfunction "4_4") (pintype "passive"))
    )
    (net (code "102") (name "Net-(PANEL_D-Pad3)") (class "Default")
      (node (ref "PANEL_D") (pin "3") (pinfunction "3_3") (pintype "passive"))
      (node (ref "S1") (pin "6") (pinfunction "6_6") (pintype "passive"))
    )
    (net (code "103") (name "Net-(PANEL_D-Pad4)") (class "Default")
      (node (ref "PANEL_D") (pin "4") (pinfunction "4_4") (pintype "passive"))
      (node (ref "S1") (pin "8") (pinfunction "8_8") (pintype "passive"))
    )
    (net (code "104") (name "Net-(PANEL_D-Pad5)") (class "Default")
      (node (ref "PANEL_D") (pin "5") (pinfunction "5_5") (pintype "passive"))
      (node (ref "S1") (pin "10") (pinfunction "10_10") (pintype "passive"))
    )
    (net (code "105") (name "Net-(PANEL_D-Pad6)") (class "Default")
      (node (ref "PANEL_D") (pin "6") (pinfunction "6_6") (pintype "passive"))
      (node (ref "S1") (pin "12") (pinfunction "12_12") (pintype "passive"))
    )
    (net (code "106") (name "Net-(PANEL_D-Pad7)") (class "Default")
      (node (ref "PANEL_D") (pin "7") (pinfunction "7_7") (pintype "passive"))
      (node (ref "S1") (pin "14") (pinfunction "14_14") (pintype "passive"))
    )
    (net (code "107") (name "Net-(PANEL_D-Pad8)") (class "Default")
      (node (ref "PANEL_D") (pin "8") (pinfunction "8_8") (pintype "passive"))
      (node (ref "S1") (pin "16") (pinfunction "16_16") (pintype "passive"))
    )
    (net (code "108") (name "unconnected-(J1-ID-Pad4)") (class "Default")
      (node (ref "J1") (pin "4") (pinfunction "ID_4") (pintype "passive+no_connect"))
    )
    (net (code "109") (name "unconnected-(P8-Pad6)") (class "Default")
      (node (ref "P8") (pin "6") (pinfunction "6_6") (pintype "passive"))
    )
    (net (code "110") (name "unconnected-(P8-Pad7)") (class "Default")
      (node (ref "P8") (pin "7") (pinfunction "7_7") (pintype "passive"))
    )
    (net (code "111") (name "unconnected-(P9-Pad7)") (class "Default")
      (node (ref "P9") (pin "7") (pinfunction "7_7") (pintype "passive"))
    )
    (net (code "112") (name "unconnected-(P9-Pad8)") (class "Default")
      (node (ref "P9") (pin "8") (pinfunction "8_8") (pintype "passive"))
    )
    (net (code "113") (name "unconnected-(P22-Pad1)") (class "Default")
      (node (ref "P22") (pin "1") (pinfunction "1_1") (pintype "passive"))
    )
    (net (code "114") (name "unconnected-(P22-Pad2)") (class "Default")
      (node (ref "P22") (pin "2") (pinfunction "2_2") (pintype "passive"))
    )
    (net (code "115") (name "unconnected-(P22-Pad3)") (class "Default")
      (node (ref "P22") (pin "3") (pinfunction "3_3") (pintype "passive"))
    )
  )
)
